# motherboard.net
KiCad netlist of a schematic drawn in EAGLE
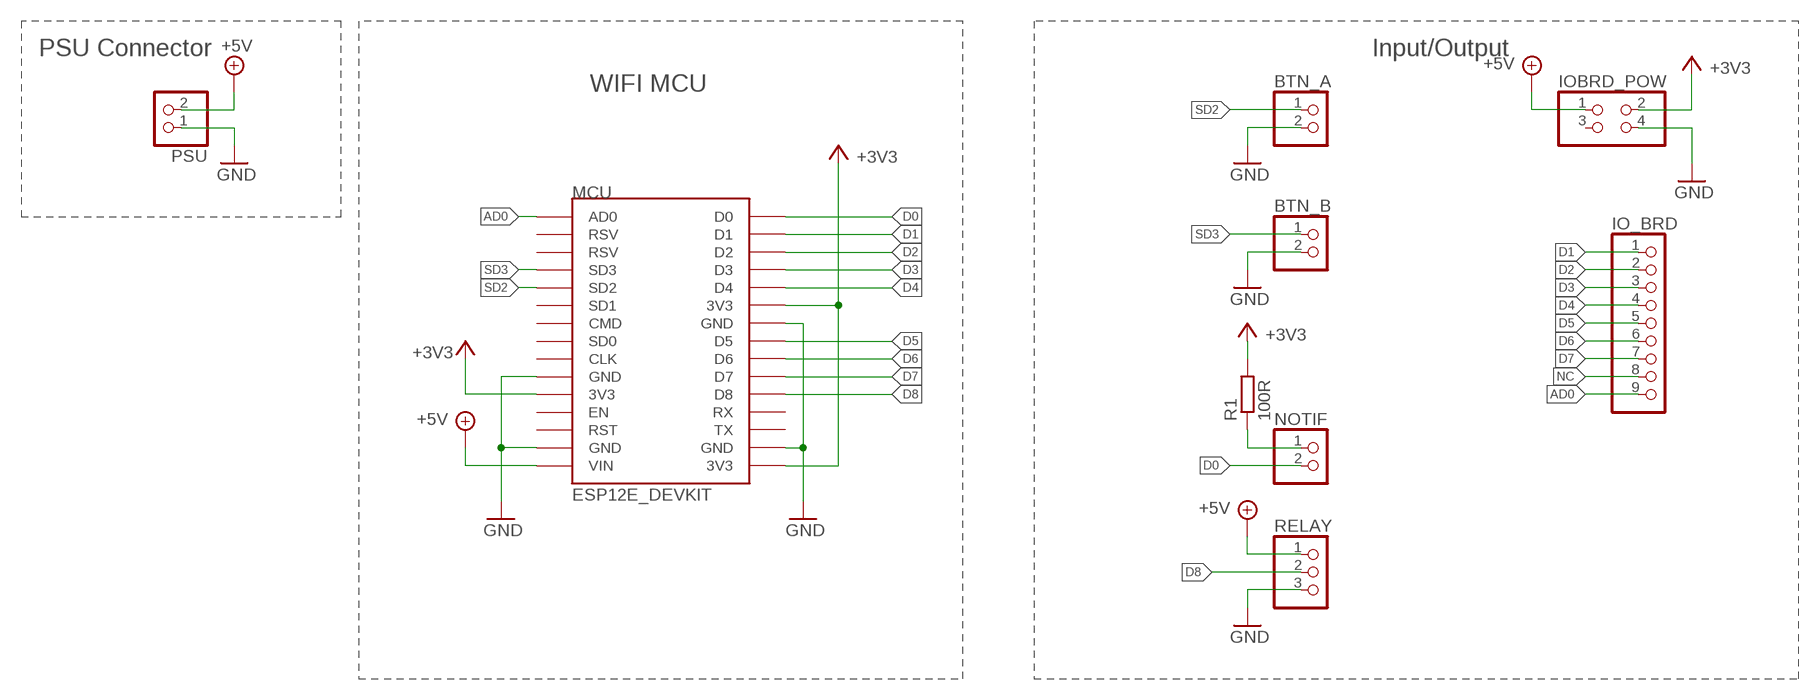
[diagram p0: schematic, sheet 1]

(export (version "E")
  (design (tool "Eeschema 10.0.6"))
  (components
    (comp (ref "BTN_A")
      (value "PINHD-1X2")
      (footprint "eagle-import:1X02")
      (libsource (lib "eagle-import") (part "PINHD-1X2"))
    )
    (comp (ref "BTN_B")
      (value "PINHD-1X2")
      (footprint "eagle-import:1X02")
      (libsource (lib "eagle-import") (part "PINHD-1X2"))
    )
    (comp (ref "IOBRD_POW")
      (value "PINHD-2X2")
      (footprint "eagle-import:2X02")
      (libsource (lib "eagle-import") (part "PINHD-2X2"))
    )
    (comp (ref "IO_BRD")
      (value "PINHD-1X9")
      (footprint "eagle-import:1X09")
      (libsource (lib "eagle-import") (part "PINHD-1X9"))
    )
    (comp (ref "MCU")
      (value "ESP12E_DEVKIT")
      (footprint "eagle-import:ESP12E_DEVKIT")
      (libsource (lib "eagle-import") (part "ESP12E_DEVKIT"))
    )
    (comp (ref "NOTIF")
      (value "PINHD-1X2")
      (footprint "eagle-import:1X02")
      (libsource (lib "eagle-import") (part "PINHD-1X2"))
    )
    (comp (ref "PSU")
      (value "PINHD-1X2")
      (footprint "eagle-import:1X02")
      (libsource (lib "eagle-import") (part "PINHD-1X2"))
    )
    (comp (ref "R1")
      (value "100R")
      (footprint "eagle-import:0204_7")
      (libsource (lib "eagle-import") (part "R-EU_0204/7"))
    )
    (comp (ref "RELAY")
      (value "PINHD-1X3")
      (footprint "eagle-import:1X03")
      (libsource (lib "eagle-import") (part "PINHD-1X3"))
    )
  )
  (nets
    (net (code "1") (name "+3V3") (class "Default")
      (node (ref "IOBRD_POW") (pin "2") (pinfunction "2_2") (pintype "passive"))
      (node (ref "MCU") (pin "3V3@0") (pinfunction "3V3_3V3@0") (pintype "bidirectional"))
      (node (ref "MCU") (pin "3V3@1") (pinfunction "3V3_3V3@1") (pintype "bidirectional"))
      (node (ref "MCU") (pin "3V3@2") (pinfunction "3V3_3V3@2") (pintype "bidirectional"))
      (node (ref "R1") (pin "2") (pinfunction "2_2") (pintype "passive"))
    )
    (net (code "2") (name "+5V") (class "Default")
      (node (ref "IOBRD_POW") (pin "1") (pinfunction "1_1") (pintype "passive"))
      (node (ref "MCU") (pin "VIN") (pinfunction "VIN_VIN") (pintype "bidirectional"))
      (node (ref "PSU") (pin "2") (pinfunction "2_2") (pintype "passive"))
      (node (ref "RELAY") (pin "1") (pinfunction "1_1") (pintype "passive"))
    )
    (net (code "3") (name "AD0") (class "Default")
      (node (ref "IO_BRD") (pin "9") (pinfunction "9_9") (pintype "passive"))
      (node (ref "MCU") (pin "AD0") (pinfunction "AD0_AD0") (pintype "bidirectional"))
    )
    (net (code "4") (name "D0") (class "Default")
      (node (ref "MCU") (pin "D0") (pinfunction "D0_D0") (pintype "bidirectional"))
      (node (ref "NOTIF") (pin "2") (pinfunction "2_2") (pintype "passive"))
    )
    (net (code "5") (name "D1") (class "Default")
      (node (ref "IO_BRD") (pin "1") (pinfunction "1_1") (pintype "passive"))
      (node (ref "MCU") (pin "D1") (pinfunction "D1_D1") (pintype "bidirectional"))
    )
    (net (code "6") (name "D2") (class "Default")
      (node (ref "IO_BRD") (pin "2") (pinfunction "2_2") (pintype "passive"))
      (node (ref "MCU") (pin "D2") (pinfunction "D2_D2") (pintype "bidirectional"))
    )
    (net (code "7") (name "D3") (class "Default")
      (node (ref "IO_BRD") (pin "3") (pinfunction "3_3") (pintype "passive"))
      (node (ref "MCU") (pin "D3") (pinfunction "D3_D3") (pintype "bidirectional"))
    )
    (net (code "8") (name "D4") (class "Default")
      (node (ref "IO_BRD") (pin "4") (pinfunction "4_4") (pintype "passive"))
      (node (ref "MCU") (pin "D4") (pinfunction "D4_D4") (pintype "bidirectional"))
    )
    (net (code "9") (name "D5") (class "Default")
      (node (ref "IO_BRD") (pin "5") (pinfunction "5_5") (pintype "passive"))
      (node (ref "MCU") (pin "D5") (pinfunction "D5_D5") (pintype "bidirectional"))
    )
    (net (code "10") (name "D6") (class "Default")
      (node (ref "IO_BRD") (pin "6") (pinfunction "6_6") (pintype "passive"))
      (node (ref "MCU") (pin "D6") (pinfunction "D6_D6") (pintype "bidirectional"))
    )
    (net (code "11") (name "D7") (class "Default")
      (node (ref "IO_BRD") (pin "7") (pinfunction "7_7") (pintype "passive"))
      (node (ref "MCU") (pin "D7") (pinfunction "D7_D7") (pintype "bidirectional"))
    )
    (net (code "12") (name "D8") (class "Default")
      (node (ref "MCU") (pin "D8") (pinfunction "D8_D8") (pintype "bidirectional"))
      (node (ref "RELAY") (pin "2") (pinfunction "2_2") (pintype "passive"))
    )
    (net (code "13") (name "GND") (class "Default")
      (node (ref "BTN_A") (pin "2") (pinfunction "2_2") (pintype "passive"))
      (node (ref "BTN_B") (pin "2") (pinfunction "2_2") (pintype "passive"))
      (node (ref "IOBRD_POW") (pin "4") (pinfunction "4_4") (pintype "passive"))
      (node (ref "MCU") (pin "GND@0") (pinfunction "GND_GND@0") (pintype "bidirectional"))
      (node (ref "MCU") (pin "GND@1") (pinfunction "GND_GND@1") (pintype "bidirectional"))
      (node (ref "MCU") (pin "GND@2") (pinfunction "GND_GND@2") (pintype "bidirectional"))
      (node (ref "MCU") (pin "GND@3") (pinfunction "GND_GND@3") (pintype "bidirectional"))
      (node (ref "PSU") (pin "1") (pinfunction "1_1") (pintype "passive"))
      (node (ref "RELAY") (pin "3") (pinfunction "3_3") (pintype "passive"))
    )
    (net (code "14") (name "NC") (class "Default")
      (node (ref "IO_BRD") (pin "8") (pinfunction "8_8") (pintype "passive"))
    )
    (net (code "15") (name "Net-(NOTIF-Pad1)") (class "Default")
      (node (ref "NOTIF") (pin "1") (pinfunction "1_1") (pintype "passive"))
      (node (ref "R1") (pin "1") (pinfunction "1_1") (pintype "passive"))
    )
    (net (code "16") (name "SD2") (class "Default")
      (node (ref "BTN_A") (pin "1") (pinfunction "1_1") (pintype "passive"))
      (node (ref "MCU") (pin "SD2") (pinfunction "SD2_SD2") (pintype "bidirectional"))
    )
    (net (code "17") (name "SD3") (class "Default")
      (node (ref "BTN_B") (pin "1") (pinfunction "1_1") (pintype "passive"))
      (node (ref "MCU") (pin "SD3") (pinfunction "SD3_SD3") (pintype "bidirectional"))
    )
    (net (code "18") (name "unconnected-(IOBRD_POW-Pad3)") (class "Default")
      (node (ref "IOBRD_POW") (pin "3") (pinfunction "3_3") (pintype "passive"))
    )
    (net (code "19") (name "unconnected-(MCU-PadCLK)") (class "Default")
      (node (ref "MCU") (pin "CLK") (pinfunction "CLK_CLK") (pintype "bidirectional"))
    )
    (net (code "20") (name "unconnected-(MCU-PadCMD)") (class "Default")
      (node (ref "MCU") (pin "CMD") (pinfunction "CMD_CMD") (pintype "bidirectional"))
    )
    (net (code "21") (name "unconnected-(MCU-PadEN)") (class "Default")
      (node (ref "MCU") (pin "EN") (pinfunction "EN_EN") (pintype "bidirectional"))
    )
    (net (code "22") (name "unconnected-(MCU-PadRST)") (class "Default")
      (node (ref "MCU") (pin "RST") (pinfunction "RST_RST") (pintype "bidirectional"))
    )
    (net (code "23") (name "unconnected-(MCU-PadRX)") (class "Default")
      (node (ref "MCU") (pin "RX") (pinfunction "RX_RX") (pintype "bidirectional"))
    )
    (net (code "24") (name "unconnected-(MCU-PadSD0)") (class "Default")
      (node (ref "MCU") (pin "SD0") (pinfunction "SD0_SD0") (pintype "bidirectional"))
    )
    (net (code "25") (name "unconnected-(MCU-PadSD1)") (class "Default")
      (node (ref "MCU") (pin "SD1") (pinfunction "SD1_SD1") (pintype "bidirectional"))
    )
    (net (code "26") (name "unconnected-(MCU-PadTX)") (class "Default")
      (node (ref "MCU") (pin "TX") (pinfunction "TX_TX") (pintype "bidirectional"))
    )
    (net (code "27") (name "unconnected-(MCU-RSV-PadRSV@0)") (class "Default")
      (node (ref "MCU") (pin "RSV@0") (pinfunction "RSV_RSV@0") (pintype "bidirectional"))
    )
    (net (code "28") (name "unconnected-(MCU-RSV-PadRSV@1)") (class "Default")
      (node (ref "MCU") (pin "RSV@1") (pinfunction "RSV_RSV@1") (pintype "bidirectional"))
    )
  )
)
